# Motor_Encoder.net
KiCad netlist of a schematic drawn in Altium Designer
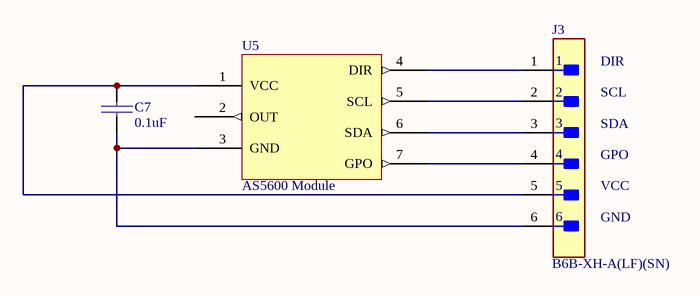
[diagram p0: Motor_Encoder.SchDoc]

(export (version "E")
  (design (tool "Eeschema 10.0.6"))
  (components
    (comp (ref "C7")
      (value "0.1uF")
      (footprint "CAP_Axial_0.2mm")
      (description "Non-Polarized Capacitor")
      (libsource (lib "ProyectoTD3") (part "CAP_NP"))
    )
    (comp (ref "J3")
      (value "B6B-XH-A(LF)(SN)")
      (footprint "JST 6 PIN CONNECTOR")
      (description "CONN HEADER VERT 6POS 2.5MM")
      (libsource (lib "ProyectoTD3") (part "JST 6 PIN"))
    )
    (comp (ref "U5")
      (value "AS5600 Module")
      (footprint "AS5600 Module")
      (description "AS5600 Magnetic Angle Sensor Encoder Module")
      (libsource (lib "ProyectoTD3") (part "AS5600 Module"))
    )
  )
  (nets
    (net (code "1") (name "Net-(U5-DIR)") (class "Default")
      (node (ref "J3") (pin "1") (pinfunction "1_1") (pintype "passive"))
      (node (ref "U5") (pin "4") (pinfunction "DIR_4") (pintype "output"))
    )
    (net (code "2") (name "Net-(U5-GND)") (class "Default")
      (node (ref "C7") (pin "2") (pinfunction "2_2") (pintype "passive"))
      (node (ref "J3") (pin "6") (pinfunction "6_6") (pintype "passive"))
      (node (ref "U5") (pin "3") (pinfunction "GND_3") (pintype "power_in"))
    )
    (net (code "3") (name "Net-(U5-GPO)") (class "Default")
      (node (ref "J3") (pin "4") (pinfunction "4_4") (pintype "passive"))
      (node (ref "U5") (pin "7") (pinfunction "GPO_7") (pintype "output"))
    )
    (net (code "4") (name "Net-(U5-SCL)") (class "Default")
      (node (ref "J3") (pin "2") (pinfunction "2_2") (pintype "passive"))
      (node (ref "U5") (pin "5") (pinfunction "SCL_5") (pintype "output"))
    )
    (net (code "5") (name "Net-(U5-SDA)") (class "Default")
      (node (ref "J3") (pin "3") (pinfunction "3_3") (pintype "passive"))
      (node (ref "U5") (pin "6") (pinfunction "SDA_6") (pintype "output"))
    )
    (net (code "6") (name "Net-(U5-VCC)") (class "Default")
      (node (ref "C7") (pin "1") (pinfunction "1_1") (pintype "passive"))
      (node (ref "J3") (pin "5") (pinfunction "5_5") (pintype "passive"))
      (node (ref "U5") (pin "1") (pinfunction "VCC_1") (pintype "power_in"))
    )
    (net (code "7") (name "unconnected-(U5-OUT-Pad2)") (class "Default")
      (node (ref "U5") (pin "2") (pinfunction "OUT_2") (pintype "output"))
    )
  )
)
